# xr_vco_components.net
KiCad netlist of a schematic drawn in EAGLE
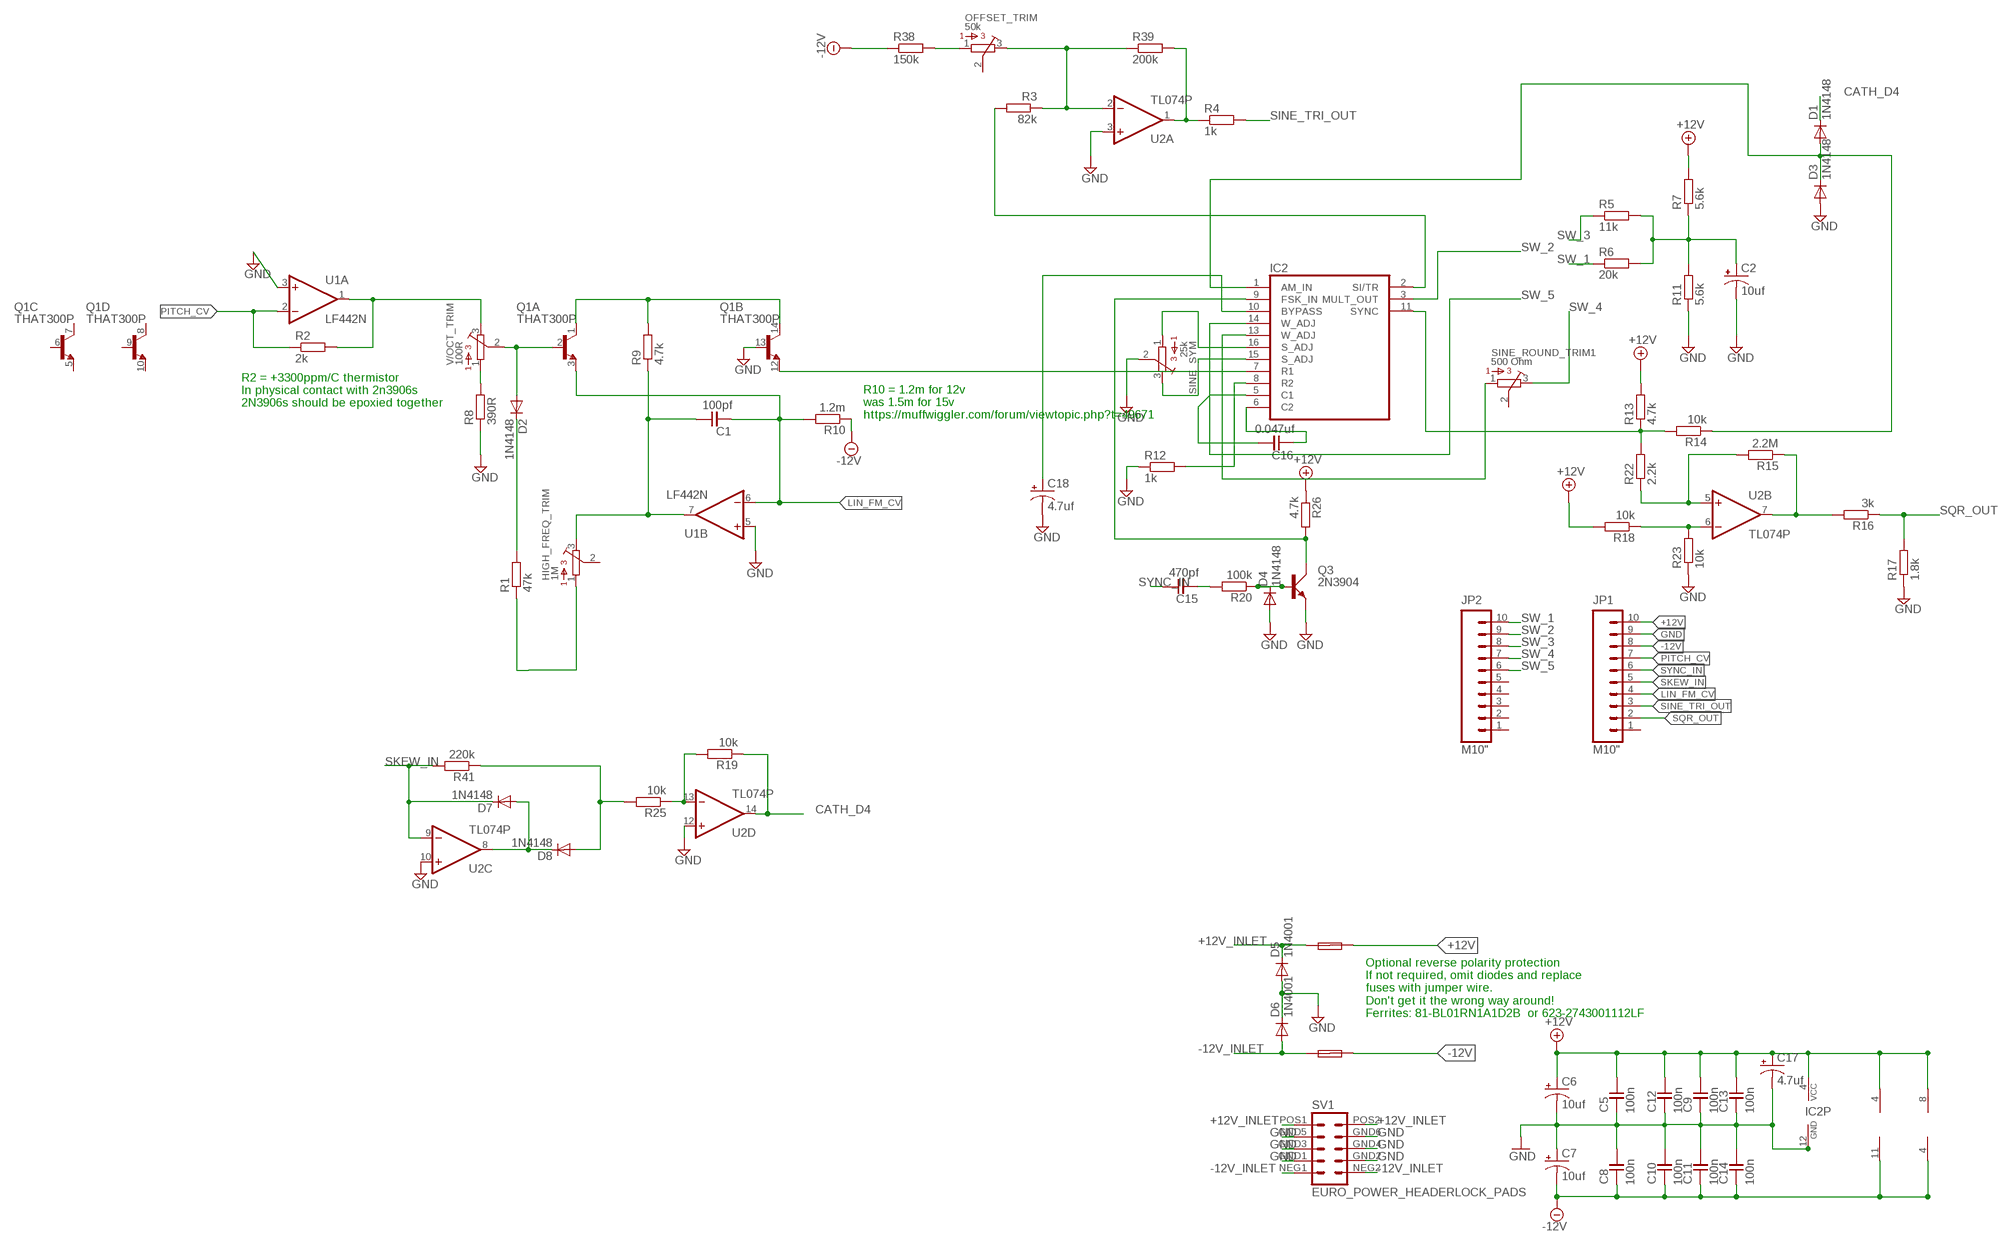
[diagram p0: schematic, sheet 1]

(export (version "E")
  (design (tool "Eeschema 10.0.6"))
  (components
    (comp (ref "C1")
      (value "100pf")
      (footprint "eagle-import:C050-024X044")
      (libsource (lib "eagle-import") (part "C-EU050-024X044"))
    )
    (comp (ref "C2")
      (value "10uf")
      (footprint "eagle-import:CPOL-RADIAL-10UF-25V")
      (libsource (lib "eagle-import") (part "CAP_POLPTH2"))
    )
    (comp (ref "C5")
      (value "100n")
      (footprint "eagle-import:C050-024X044")
      (libsource (lib "eagle-import") (part "C-EU050-024X044"))
    )
    (comp (ref "C6")
      (value "10uf")
      (footprint "eagle-import:CPOL-RADIAL-10UF-25V")
      (libsource (lib "eagle-import") (part "CAP_POLPTH2"))
    )
    (comp (ref "C7")
      (value "10uf")
      (footprint "eagle-import:CPOL-RADIAL-10UF-25V")
      (libsource (lib "eagle-import") (part "CAP_POLPTH2"))
    )
    (comp (ref "C8")
      (value "100n")
      (footprint "eagle-import:C050-024X044")
      (libsource (lib "eagle-import") (part "C-EU050-024X044"))
    )
    (comp (ref "C9")
      (value "100n")
      (footprint "eagle-import:C050-024X044")
      (libsource (lib "eagle-import") (part "C-EU050-024X044"))
    )
    (comp (ref "C10")
      (value "100n")
      (footprint "eagle-import:C050-024X044")
      (libsource (lib "eagle-import") (part "C-EU050-024X044"))
    )
    (comp (ref "C11")
      (value "100n")
      (footprint "eagle-import:C050-024X044")
      (libsource (lib "eagle-import") (part "C-EU050-024X044"))
    )
    (comp (ref "C12")
      (value "100n")
      (footprint "eagle-import:C050-024X044")
      (libsource (lib "eagle-import") (part "C-EU050-024X044"))
    )
    (comp (ref "C13")
      (value "100n")
      (footprint "eagle-import:C050-024X044")
      (libsource (lib "eagle-import") (part "C-EU050-024X044"))
    )
    (comp (ref "C14")
      (value "100n")
      (footprint "eagle-import:C050-024X044")
      (libsource (lib "eagle-import") (part "C-EU050-024X044"))
    )
    (comp (ref "C15")
      (value "470pf")
      (footprint "eagle-import:C050-024X044")
      (libsource (lib "eagle-import") (part "C-EU050-024X044"))
    )
    (comp (ref "C16")
      (value "0.047uf")
      (footprint "eagle-import:C050-024X044")
      (libsource (lib "eagle-import") (part "C-EU050-024X044"))
    )
    (comp (ref "C17")
      (value "4.7uf")
      (footprint "eagle-import:CPOL-RADIAL-10UF-25V")
      (libsource (lib "eagle-import") (part "CAP_POLPTH2"))
    )
    (comp (ref "C18")
      (value "4.7uf")
      (footprint "eagle-import:CPOL-RADIAL-10UF-25V")
      (libsource (lib "eagle-import") (part "CAP_POLPTH2"))
    )
    (comp (ref "D1")
      (value "1N4148")
      (footprint "eagle-import:DO35-7")
      (libsource (lib "eagle-import") (part "SMALL_DIODEDO35-7"))
    )
    (comp (ref "D2")
      (value "1N4148")
      (footprint "eagle-import:DO35-7")
      (libsource (lib "eagle-import") (part "SMALL_DIODEDO35-7"))
    )
    (comp (ref "D3")
      (value "1N4148")
      (footprint "eagle-import:DO35-7")
      (libsource (lib "eagle-import") (part "SMALL_DIODEDO35-7"))
    )
    (comp (ref "D4")
      (value "1N4148")
      (footprint "eagle-import:DO35-7")
      (libsource (lib "eagle-import") (part "SMALL_DIODEDO35-7"))
    )
    (comp (ref "D5")
      (value "1N4001")
      (footprint "eagle-import:DO41-10")
      (libsource (lib "eagle-import") (part "1N4004"))
    )
    (comp (ref "D6")
      (value "1N4001")
      (footprint "eagle-import:DO41-10")
      (libsource (lib "eagle-import") (part "1N4004"))
    )
    (comp (ref "D7")
      (value "1N4148")
      (footprint "eagle-import:DO35-7")
      (libsource (lib "eagle-import") (part "SMALL_DIODEDO35-7"))
    )
    (comp (ref "D8")
      (value "1N4148")
      (footprint "eagle-import:DO35-7")
      (libsource (lib "eagle-import") (part "SMALL_DIODEDO35-7"))
    )
    (comp (ref "F1")
      (value "FUSE")
      (footprint "eagle-import:C050H075X075")
      (libsource (lib "eagle-import") (part "PTC_FUSEPOLY_FUSE"))
    )
    (comp (ref "F2")
      (value "FUSE")
      (footprint "eagle-import:C050H075X075")
      (libsource (lib "eagle-import") (part "PTC_FUSEPOLY_FUSE"))
    )
    (comp (ref "HIGH_FREQ_TRIM")
      (value "1M")
      (footprint "eagle-import:BOURNS_3362P_TRIMMER")
      (libsource (lib "eagle-import") (part "BOURNS_3362P_TRIMMERP"))
    )
    (comp (ref "IC2")
      (value "XR-2206")
      (footprint "eagle-import:DIL16")
      (libsource (lib "eagle-import") (part "XR-2206"))
    )
    (comp (ref "JP1")
      (value "M10\"")
      (footprint "eagle-import:1X10")
      (libsource (lib "eagle-import") (part "M10{dblquote}"))
    )
    (comp (ref "JP2")
      (value "M10\"")
      (footprint "eagle-import:1X10")
      (libsource (lib "eagle-import") (part "M10{dblquote}"))
    )
    (comp (ref "OFFSET_TRIM")
      (value "50k")
      (footprint "eagle-import:BOURNS_3362P_TRIMMER")
      (libsource (lib "eagle-import") (part "BOURNS_3362P_TRIMMERP"))
    )
    (comp (ref "Q1")
      (value "THAT300P")
      (footprint "eagle-import:DIL14")
      (libsource (lib "eagle-import") (part "THAT300P"))
    )
    (comp (ref "Q3")
      (value "2N3904")
      (footprint "eagle-import:TO92D")
      (libsource (lib "eagle-import") (part "2N3904"))
    )
    (comp (ref "R1")
      (value "47k")
      (footprint "eagle-import:7MM_RESISTOR")
      (libsource (lib "eagle-import") (part "RESISTOR7MM"))
    )
    (comp (ref "R2")
      (value "2k")
      (footprint "eagle-import:7MM_RESISTOR")
      (libsource (lib "eagle-import") (part "RESISTOR7MM"))
    )
    (comp (ref "R3")
      (value "82k")
      (footprint "eagle-import:7MM_RESISTOR")
      (libsource (lib "eagle-import") (part "RESISTOR7MM"))
    )
    (comp (ref "R4")
      (value "1k")
      (footprint "eagle-import:7MM_RESISTOR")
      (libsource (lib "eagle-import") (part "RESISTOR7MM"))
    )
    (comp (ref "R5")
      (value "11k")
      (footprint "eagle-import:7MM_RESISTOR")
      (libsource (lib "eagle-import") (part "RESISTOR7MM"))
    )
    (comp (ref "R6")
      (value "20k")
      (footprint "eagle-import:7MM_RESISTOR")
      (libsource (lib "eagle-import") (part "RESISTOR7MM"))
    )
    (comp (ref "R7")
      (value "5.6k")
      (footprint "eagle-import:7MM_RESISTOR")
      (libsource (lib "eagle-import") (part "RESISTOR7MM"))
    )
    (comp (ref "R8")
      (value "390R")
      (footprint "eagle-import:7MM_RESISTOR")
      (libsource (lib "eagle-import") (part "RESISTOR7MM"))
    )
    (comp (ref "R9")
      (value "4.7k")
      (footprint "eagle-import:7MM_RESISTOR")
      (libsource (lib "eagle-import") (part "RESISTOR7MM"))
    )
    (comp (ref "R10")
      (value "1.2m")
      (footprint "eagle-import:7MM_RESISTOR")
      (libsource (lib "eagle-import") (part "RESISTOR7MM"))
    )
    (comp (ref "R11")
      (value "5.6k")
      (footprint "eagle-import:7MM_RESISTOR")
      (libsource (lib "eagle-import") (part "RESISTOR7MM"))
    )
    (comp (ref "R12")
      (value "1k")
      (footprint "eagle-import:7MM_RESISTOR")
      (libsource (lib "eagle-import") (part "RESISTOR7MM"))
    )
    (comp (ref "R13")
      (value "4.7k")
      (footprint "eagle-import:7MM_RESISTOR")
      (libsource (lib "eagle-import") (part "RESISTOR7MM"))
    )
    (comp (ref "R14")
      (value "10k")
      (footprint "eagle-import:7MM_RESISTOR")
      (libsource (lib "eagle-import") (part "RESISTOR7MM"))
    )
    (comp (ref "R15")
      (value "2.2M")
      (footprint "eagle-import:7MM_RESISTOR")
      (libsource (lib "eagle-import") (part "RESISTOR7MM"))
    )
    (comp (ref "R16")
      (value "3k")
      (footprint "eagle-import:7MM_RESISTOR")
      (libsource (lib "eagle-import") (part "RESISTOR7MM"))
    )
    (comp (ref "R17")
      (value "1.8k")
      (footprint "eagle-import:7MM_RESISTOR")
      (libsource (lib "eagle-import") (part "RESISTOR7MM"))
    )
    (comp (ref "R18")
      (value "10k")
      (footprint "eagle-import:7MM_RESISTOR")
      (libsource (lib "eagle-import") (part "RESISTOR7MM"))
    )
    (comp (ref "R19")
      (value "10k")
      (footprint "eagle-import:7MM_RESISTOR")
      (libsource (lib "eagle-import") (part "RESISTOR7MM"))
    )
    (comp (ref "R20")
      (value "100k")
      (footprint "eagle-import:7MM_RESISTOR")
      (libsource (lib "eagle-import") (part "RESISTOR7MM"))
    )
    (comp (ref "R22")
      (value "2.2k")
      (footprint "eagle-import:7MM_RESISTOR")
      (libsource (lib "eagle-import") (part "RESISTOR7MM"))
    )
    (comp (ref "R23")
      (value "10k")
      (footprint "eagle-import:7MM_RESISTOR")
      (libsource (lib "eagle-import") (part "RESISTOR7MM"))
    )
    (comp (ref "R25")
      (value "10k")
      (footprint "eagle-import:7MM_RESISTOR")
      (libsource (lib "eagle-import") (part "RESISTOR7MM"))
    )
    (comp (ref "R26")
      (value "4.7k")
      (footprint "eagle-import:7MM_RESISTOR")
      (libsource (lib "eagle-import") (part "RESISTOR7MM"))
    )
    (comp (ref "R38")
      (value "150k")
      (footprint "eagle-import:7MM_RESISTOR")
      (libsource (lib "eagle-import") (part "RESISTOR7MM"))
    )
    (comp (ref "R39")
      (value "200k")
      (footprint "eagle-import:7MM_RESISTOR")
      (libsource (lib "eagle-import") (part "RESISTOR7MM"))
    )
    (comp (ref "R41")
      (value "220k")
      (footprint "eagle-import:7MM_RESISTOR")
      (libsource (lib "eagle-import") (part "RESISTOR7MM"))
    )
    (comp (ref "SINE_ROUND_TRIM1")
      (value "500 Ohm")
      (footprint "eagle-import:BOURNS_3362P_TRIMMER")
      (libsource (lib "eagle-import") (part "BOURNS_3362P_TRIMMERP"))
    )
    (comp (ref "SINE_SYM")
      (value "25k")
      (footprint "eagle-import:BOURNS_3362P_TRIMMER")
      (libsource (lib "eagle-import") (part "BOURNS_3362P_TRIMMERP"))
    )
    (comp (ref "SV1")
      (value "EURO_POWER_HEADERLOCK_PADS")
      (footprint "eagle-import:EURO_PWR_HEADER_LOCK")
      (libsource (lib "eagle-import") (part "EURO_POWER_HEADERLOCK_PADS"))
    )
    (comp (ref "U1")
      (value "LF442N")
      (footprint "eagle-import:DIL08")
      (libsource (lib "eagle-import") (part "LF442N"))
    )
    (comp (ref "U2")
      (value "TL074P")
      (footprint "eagle-import:DIL14")
      (libsource (lib "eagle-import") (part "TL074P"))
    )
    (comp (ref "V/OCT_TRIM")
      (value "100R")
      (footprint "eagle-import:BOURNS_3362P_TRIMMER")
      (libsource (lib "eagle-import") (part "BOURNS_3362P_TRIMMERP"))
    )
  )
  (nets
    (net (code "1") (name "+12V") (class "Default")
      (node (ref "C12") (pin "1") (pinfunction "1_1") (pintype "passive"))
      (node (ref "C13") (pin "1") (pinfunction "1_1") (pintype "passive"))
      (node (ref "C17") (pin "1") (pinfunction "+_1") (pintype "passive"))
      (node (ref "C5") (pin "1") (pinfunction "1_1") (pintype "passive"))
      (node (ref "C6") (pin "1") (pinfunction "+_1") (pintype "passive"))
      (node (ref "C9") (pin "1") (pinfunction "1_1") (pintype "passive"))
      (node (ref "F1") (pin "2") (pinfunction "P$2_2") (pintype "bidirectional"))
      (node (ref "IC2") (pin "4") (pinfunction "VCC_4") (pintype "power_in"))
      (node (ref "JP1") (pin "10") (pinfunction "10_10") (pintype "passive"))
      (node (ref "R13") (pin "2") (pinfunction "2_2") (pintype "passive"))
      (node (ref "R18") (pin "2") (pinfunction "2_2") (pintype "passive"))
      (node (ref "R26") (pin "1") (pinfunction "1_1") (pintype "passive"))
      (node (ref "R7") (pin "2") (pinfunction "2_2") (pintype "passive"))
      (node (ref "U1") (pin "8") (pinfunction "V+_8") (pintype "power_in"))
      (node (ref "U2") (pin "4") (pinfunction "V+_4") (pintype "power_in"))
    )
    (net (code "2") (name "-12V") (class "Default")
      (node (ref "C10") (pin "2") (pinfunction "2_2") (pintype "passive"))
      (node (ref "C11") (pin "2") (pinfunction "2_2") (pintype "passive"))
      (node (ref "C14") (pin "2") (pinfunction "2_2") (pintype "passive"))
      (node (ref "C7") (pin "2") (pinfunction "-_2") (pintype "passive"))
      (node (ref "C8") (pin "2") (pinfunction "2_2") (pintype "passive"))
      (node (ref "F2") (pin "2") (pinfunction "P$2_2") (pintype "bidirectional"))
      (node (ref "JP1") (pin "8") (pinfunction "8_8") (pintype "passive"))
      (node (ref "R10") (pin "1") (pinfunction "1_1") (pintype "passive"))
      (node (ref "R38") (pin "1") (pinfunction "1_1") (pintype "passive"))
      (node (ref "U1") (pin "4") (pinfunction "V-_4") (pintype "power_in"))
      (node (ref "U2") (pin "11") (pinfunction "V-_11") (pintype "power_in"))
    )
    (net (code "3") (name "/+12V_INLET") (class "Default")
      (node (ref "D5") (pin "C") (pinfunction "C_C") (pintype "passive"))
      (node (ref "F1") (pin "1") (pinfunction "P$1_1") (pintype "bidirectional"))
      (node (ref "SV1") (pin "POS1") (pinfunction "10_POS1") (pintype "passive"))
      (node (ref "SV1") (pin "POS2") (pinfunction "9_POS2") (pintype "passive"))
    )
    (net (code "4") (name "/-12V_INLET") (class "Default")
      (node (ref "D6") (pin "A") (pinfunction "A_A") (pintype "passive"))
      (node (ref "F2") (pin "1") (pinfunction "P$1_1") (pintype "bidirectional"))
      (node (ref "SV1") (pin "NEG1") (pinfunction "2_NEG1") (pintype "passive"))
      (node (ref "SV1") (pin "NEG2") (pinfunction "1_NEG2") (pintype "passive"))
    )
    (net (code "5") (name "/CATH_D4") (class "Default")
      (node (ref "D1") (pin "C") (pinfunction "C_C") (pintype "passive"))
      (node (ref "R19") (pin "1") (pinfunction "1_1") (pintype "passive"))
      (node (ref "U2") (pin "14") (pinfunction "OUT_14") (pintype "output"))
    )
    (net (code "6") (name "/SW_1") (class "Default")
      (node (ref "JP2") (pin "10") (pinfunction "10_10") (pintype "passive"))
      (node (ref "R6") (pin "1") (pinfunction "1_1") (pintype "passive"))
    )
    (net (code "7") (name "/SW_2") (class "Default")
      (node (ref "IC2") (pin "3") (pinfunction "MULT_OUT_3") (pintype "output"))
      (node (ref "JP2") (pin "9") (pinfunction "9_9") (pintype "passive"))
    )
    (net (code "8") (name "/SW_3") (class "Default")
      (node (ref "JP2") (pin "8") (pinfunction "8_8") (pintype "passive"))
      (node (ref "R5") (pin "1") (pinfunction "1_1") (pintype "passive"))
    )
    (net (code "9") (name "/SW_4") (class "Default")
      (node (ref "JP2") (pin "7") (pinfunction "7_7") (pintype "passive"))
      (node (ref "SINE_ROUND_TRIM1") (pin "3") (pinfunction "3_3") (pintype "passive"))
    )
    (net (code "10") (name "/SW_5") (class "Default")
      (node (ref "IC2") (pin "14") (pinfunction "W_ADJ_14") (pintype "input"))
      (node (ref "JP2") (pin "6") (pinfunction "6_6") (pintype "passive"))
    )
    (net (code "11") (name "GND") (class "Default")
      (node (ref "C10") (pin "1") (pinfunction "1_1") (pintype "passive"))
      (node (ref "C11") (pin "1") (pinfunction "1_1") (pintype "passive"))
      (node (ref "C12") (pin "2") (pinfunction "2_2") (pintype "passive"))
      (node (ref "C13") (pin "2") (pinfunction "2_2") (pintype "passive"))
      (node (ref "C14") (pin "1") (pinfunction "1_1") (pintype "passive"))
      (node (ref "C17") (pin "2") (pinfunction "-_2") (pintype "passive"))
      (node (ref "C18") (pin "2") (pinfunction "-_2") (pintype "passive"))
      (node (ref "C2") (pin "2") (pinfunction "-_2") (pintype "passive"))
      (node (ref "C5") (pin "2") (pinfunction "2_2") (pintype "passive"))
      (node (ref "C6") (pin "2") (pinfunction "-_2") (pintype "passive"))
      (node (ref "C7") (pin "1") (pinfunction "+_1") (pintype "passive"))
      (node (ref "C8") (pin "1") (pinfunction "1_1") (pintype "passive"))
      (node (ref "C9") (pin "2") (pinfunction "2_2") (pintype "passive"))
      (node (ref "D3") (pin "A") (pinfunction "A_A") (pintype "passive"))
      (node (ref "D4") (pin "A") (pinfunction "A_A") (pintype "passive"))
      (node (ref "D5") (pin "A") (pinfunction "A_A") (pintype "passive"))
      (node (ref "D6") (pin "C") (pinfunction "C_C") (pintype "passive"))
      (node (ref "IC2") (pin "12") (pinfunction "GND_12") (pintype "power_in"))
      (node (ref "JP1") (pin "9") (pinfunction "9_9") (pintype "passive"))
      (node (ref "Q1") (pin "13") (pinfunction "B_13") (pintype "passive"))
      (node (ref "Q3") (pin "E") (pinfunction "E_E") (pintype "passive"))
      (node (ref "R11") (pin "1") (pinfunction "1_1") (pintype "passive"))
      (node (ref "R12") (pin "1") (pinfunction "1_1") (pintype "passive"))
      (node (ref "R17") (pin "1") (pinfunction "1_1") (pintype "passive"))
      (node (ref "R23") (pin "1") (pinfunction "1_1") (pintype "passive"))
      (node (ref "R8") (pin "1") (pinfunction "1_1") (pintype "passive"))
      (node (ref "SINE_SYM") (pin "2") (pinfunction "2_2") (pintype "passive"))
      (node (ref "SV1") (pin "GND1") (pinfunction "4_GND1") (pintype "passive"))
      (node (ref "SV1") (pin "GND2") (pinfunction "3_GND2") (pintype "passive"))
      (node (ref "SV1") (pin "GND3") (pinfunction "6_GND3") (pintype "passive"))
      (node (ref "SV1") (pin "GND4") (pinfunction "5_GND4") (pintype "passive"))
      (node (ref "SV1") (pin "GND5") (pinfunction "8_GND5") (pintype "passive"))
      (node (ref "SV1") (pin "GND6") (pinfunction "7_GND6") (pintype "passive"))
      (node (ref "U1") (pin "3") (pinfunction "+IN_3") (pintype "input"))
      (node (ref "U1") (pin "5") (pinfunction "+IN_5") (pintype "input"))
      (node (ref "U2") (pin "10") (pinfunction "+IN_10") (pintype "input"))
      (node (ref "U2") (pin "12") (pinfunction "+IN_12") (pintype "input"))
      (node (ref "U2") (pin "3") (pinfunction "+IN_3") (pintype "input"))
    )
    (net (code "12") (name "LIN_FM_CV") (class "Default")
      (node (ref "C1") (pin "2") (pinfunction "2_2") (pintype "passive"))
      (node (ref "JP1") (pin "4") (pinfunction "4_4") (pintype "passive"))
      (node (ref "Q1") (pin "3") (pinfunction "E_3") (pintype "passive"))
      (node (ref "R10") (pin "2") (pinfunction "2_2") (pintype "passive"))
      (node (ref "U1") (pin "6") (pinfunction "-IN_6") (pintype "input"))
    )
    (net (code "13") (name "Net-(C2-+)") (class "Default")
      (node (ref "C2") (pin "1") (pinfunction "+_1") (pintype "passive"))
      (node (ref "R11") (pin "2") (pinfunction "2_2") (pintype "passive"))
      (node (ref "R5") (pin "2") (pinfunction "2_2") (pintype "passive"))
      (node (ref "R6") (pin "2") (pinfunction "2_2") (pintype "passive"))
      (node (ref "R7") (pin "1") (pinfunction "1_1") (pintype "passive"))
    )
    (net (code "14") (name "Net-(C15-Pad2)") (class "Default")
      (node (ref "C15") (pin "2") (pinfunction "2_2") (pintype "passive"))
      (node (ref "R20") (pin "2") (pinfunction "2_2") (pintype "passive"))
    )
    (net (code "15") (name "Net-(C18-+)") (class "Default")
      (node (ref "C18") (pin "1") (pinfunction "+_1") (pintype "passive"))
      (node (ref "IC2") (pin "10") (pinfunction "BYPASS_10") (pintype "input"))
    )
    (net (code "16") (name "Net-(D2-PadC)") (class "Default")
      (node (ref "D2") (pin "C") (pinfunction "C_C") (pintype "passive"))
      (node (ref "R1") (pin "2") (pinfunction "2_2") (pintype "passive"))
    )
    (net (code "17") (name "Net-(D4-PadC)") (class "Default")
      (node (ref "D4") (pin "C") (pinfunction "C_C") (pintype "passive"))
      (node (ref "Q3") (pin "B") (pinfunction "B_B") (pintype "passive"))
      (node (ref "R20") (pin "1") (pinfunction "1_1") (pintype "passive"))
    )
    (net (code "18") (name "Net-(D8-PadA)") (class "Default")
      (node (ref "D8") (pin "A") (pinfunction "A_A") (pintype "passive"))
      (node (ref "R25") (pin "2") (pinfunction "2_2") (pintype "passive"))
      (node (ref "R41") (pin "1") (pinfunction "1_1") (pintype "passive"))
    )
    (net (code "19") (name "Net-(HIGH_FREQ_TRIM-Pad1)") (class "Default")
      (node (ref "HIGH_FREQ_TRIM") (pin "1") (pinfunction "1_1") (pintype "passive"))
      (node (ref "R1") (pin "1") (pinfunction "1_1") (pintype "passive"))
    )
    (net (code "20") (name "Net-(IC2A-AM_IN)") (class "Default")
      (node (ref "D1") (pin "A") (pinfunction "A_A") (pintype "passive"))
      (node (ref "D3") (pin "C") (pinfunction "C_C") (pintype "passive"))
      (node (ref "IC2") (pin "1") (pinfunction "AM_IN_1") (pintype "input"))
      (node (ref "R14") (pin "1") (pinfunction "1_1") (pintype "passive"))
    )
    (net (code "21") (name "Net-(IC2A-C1)") (class "Default")
      (node (ref "C16") (pin "1") (pinfunction "1_1") (pintype "passive"))
      (node (ref "IC2") (pin "5") (pinfunction "C1_5") (pintype "input"))
    )
    (net (code "22") (name "Net-(IC2A-C2)") (class "Default")
      (node (ref "C16") (pin "2") (pinfunction "2_2") (pintype "passive"))
      (node (ref "IC2") (pin "6") (pinfunction "C2_6") (pintype "input"))
    )
    (net (code "23") (name "Net-(IC2A-FSK_IN)") (class "Default")
      (node (ref "IC2") (pin "9") (pinfunction "FSK_IN_9") (pintype "input"))
      (node (ref "Q3") (pin "C") (pinfunction "C_C") (pintype "passive"))
      (node (ref "R26") (pin "2") (pinfunction "2_2") (pintype "passive"))
    )
    (net (code "24") (name "Net-(IC2A-R1)") (class "Default")
      (node (ref "IC2") (pin "7") (pinfunction "R1_7") (pintype "input"))
      (node (ref "Q1") (pin "12") (pinfunction "E_12") (pintype "passive"))
    )
    (net (code "25") (name "Net-(IC2A-R2)") (class "Default")
      (node (ref "IC2") (pin "8") (pinfunction "R2_8") (pintype "input"))
      (node (ref "R12") (pin "2") (pinfunction "2_2") (pintype "passive"))
    )
    (net (code "26") (name "Net-(IC2A-SI{slash}TR)") (class "Default")
      (node (ref "IC2") (pin "2") (pinfunction "SI/TR_2") (pintype "output"))
      (node (ref "R3") (pin "2") (pinfunction "2_2") (pintype "passive"))
    )
    (net (code "27") (name "Net-(IC2A-SYNC)") (class "Default")
      (node (ref "IC2") (pin "11") (pinfunction "SYNC_11") (pintype "output"))
      (node (ref "R13") (pin "1") (pinfunction "1_1") (pintype "passive"))
      (node (ref "R14") (pin "2") (pinfunction "2_2") (pintype "passive"))
      (node (ref "R22") (pin "2") (pinfunction "2_2") (pintype "passive"))
    )
    (net (code "28") (name "Net-(IC2A-S_ADJ-Pad15)") (class "Default")
      (node (ref "IC2") (pin "15") (pinfunction "S_ADJ_15") (pintype "input"))
      (node (ref "SINE_SYM") (pin "3") (pinfunction "3_3") (pintype "passive"))
    )
    (net (code "29") (name "Net-(IC2A-S_ADJ-Pad16)") (class "Default")
      (node (ref "IC2") (pin "16") (pinfunction "S_ADJ_16") (pintype "input"))
      (node (ref "SINE_SYM") (pin "1") (pinfunction "1_1") (pintype "passive"))
    )
    (net (code "30") (name "Net-(IC2A-W_ADJ-Pad13)") (class "Default")
      (node (ref "IC2") (pin "13") (pinfunction "W_ADJ_13") (pintype "input"))
      (node (ref "SINE_ROUND_TRIM1") (pin "1") (pinfunction "1_1") (pintype "passive"))
    )
    (net (code "31") (name "Net-(OFFSET_TRIM-Pad1)") (class "Default")
      (node (ref "OFFSET_TRIM") (pin "1") (pinfunction "1_1") (pintype "passive"))
      (node (ref "R38") (pin "2") (pinfunction "2_2") (pintype "passive"))
    )
    (net (code "32") (name "Net-(Q1A-B)") (class "Default")
      (node (ref "D2") (pin "A") (pinfunction "A_A") (pintype "passive"))
      (node (ref "Q1") (pin "2") (pinfunction "B_2") (pintype "passive"))
      (node (ref "V/OCT_TRIM") (pin "2") (pinfunction "2_2") (pintype "passive"))
    )
    (net (code "33") (name "Net-(Q1A-C)") (class "Default")
      (node (ref "Q1") (pin "1") (pinfunction "C_1") (pintype "passive"))
      (node (ref "Q1") (pin "14") (pinfunction "C_14") (pintype "passive"))
      (node (ref "R9") (pin "2") (pinfunction "2_2") (pintype "passive"))
    )
    (net (code "34") (name "Net-(R8-Pad2)") (class "Default")
      (node (ref "R8") (pin "2") (pinfunction "2_2") (pintype "passive"))
      (node (ref "V/OCT_TRIM") (pin "1") (pinfunction "1_1") (pintype "passive"))
    )
    (net (code "35") (name "Net-(U1A-OUT)") (class "Default")
      (node (ref "R2") (pin "2") (pinfunction "2_2") (pintype "passive"))
      (node (ref "U1") (pin "1") (pinfunction "OUT_1") (pintype "output"))
      (node (ref "V/OCT_TRIM") (pin "3") (pinfunction "3_3") (pintype "passive"))
    )
    (net (code "36") (name "Net-(U1B-OUT)") (class "Default")
      (node (ref "C1") (pin "1") (pinfunction "1_1") (pintype "passive"))
      (node (ref "HIGH_FREQ_TRIM") (pin "3") (pinfunction "3_3") (pintype "passive"))
      (node (ref "R9") (pin "1") (pinfunction "1_1") (pintype "passive"))
      (node (ref "U1") (pin "7") (pinfunction "OUT_7") (pintype "output"))
    )
    (net (code "37") (name "Net-(U2A--IN)") (class "Default")
      (node (ref "OFFSET_TRIM") (pin "3") (pinfunction "3_3") (pintype "passive"))
      (node (ref "R3") (pin "1") (pinfunction "1_1") (pintype "passive"))
      (node (ref "R39") (pin "1") (pinfunction "1_1") (pintype "passive"))
      (node (ref "U2") (pin "2") (pinfunction "-IN_2") (pintype "input"))
    )
    (net (code "38") (name "Net-(U2A-OUT)") (class "Default")
      (node (ref "R39") (pin "2") (pinfunction "2_2") (pintype "passive"))
      (node (ref "R4") (pin "1") (pinfunction "1_1") (pintype "passive"))
      (node (ref "U2") (pin "1") (pinfunction "OUT_1") (pintype "output"))
    )
    (net (code "39") (name "Net-(U2B-+IN)") (class "Default")
      (node (ref "R15") (pin "2") (pinfunction "2_2") (pintype "passive"))
      (node (ref "R22") (pin "1") (pinfunction "1_1") (pintype "passive"))
      (node (ref "U2") (pin "5") (pinfunction "+IN_5") (pintype "input"))
    )
    (net (code "40") (name "Net-(U2B--IN)") (class "Default")
      (node (ref "R18") (pin "1") (pinfunction "1_1") (pintype "passive"))
      (node (ref "R23") (pin "2") (pinfunction "2_2") (pintype "passive"))
      (node (ref "U2") (pin "6") (pinfunction "-IN_6") (pintype "input"))
    )
    (net (code "41") (name "Net-(U2B-OUT)") (class "Default")
      (node (ref "R15") (pin "1") (pinfunction "1_1") (pintype "passive"))
      (node (ref "R16") (pin "2") (pinfunction "2_2") (pintype "passive"))
      (node (ref "U2") (pin "7") (pinfunction "OUT_7") (pintype "output"))
    )
    (net (code "42") (name "Net-(U2C-OUT)") (class "Default")
      (node (ref "D7") (pin "A") (pinfunction "A_A") (pintype "passive"))
      (node (ref "D8") (pin "C") (pinfunction "C_C") (pintype "passive"))
      (node (ref "U2") (pin "8") (pinfunction "OUT_8") (pintype "output"))
    )
    (net (code "43") (name "Net-(U2D--IN)") (class "Default")
      (node (ref "R19") (pin "2") (pinfunction "2_2") (pintype "passive"))
      (node (ref "R25") (pin "1") (pinfunction "1_1") (pintype "passive"))
      (node (ref "U2") (pin "13") (pinfunction "-IN_13") (pintype "input"))
    )
    (net (code "44") (name "PITCH_CV") (class "Default")
      (node (ref "JP1") (pin "7") (pinfunction "7_7") (pintype "passive"))
      (node (ref "R2") (pin "1") (pinfunction "1_1") (pintype "passive"))
      (node (ref "U1") (pin "2") (pinfunction "-IN_2") (pintype "input"))
    )
    (net (code "45") (name "SINE_TRI_OUT") (class "Default")
      (node (ref "JP1") (pin "3") (pinfunction "3_3") (pintype "passive"))
      (node (ref "R4") (pin "2") (pinfunction "2_2") (pintype "passive"))
    )
    (net (code "46") (name "SKEW_IN") (class "Default")
      (node (ref "D7") (pin "C") (pinfunction "C_C") (pintype "passive"))
      (node (ref "JP1") (pin "5") (pinfunction "5_5") (pintype "passive"))
      (node (ref "R41") (pin "2") (pinfunction "2_2") (pintype "passive"))
      (node (ref "U2") (pin "9") (pinfunction "-IN_9") (pintype "input"))
    )
    (net (code "47") (name "SQR_OUT") (class "Default")
      (node (ref "JP1") (pin "2") (pinfunction "2_2") (pintype "passive"))
      (node (ref "R16") (pin "1") (pinfunction "1_1") (pintype "passive"))
      (node (ref "R17") (pin "2") (pinfunction "2_2") (pintype "passive"))
    )
    (net (code "48") (name "SYNC_IN") (class "Default")
      (node (ref "C15") (pin "1") (pinfunction "1_1") (pintype "passive"))
      (node (ref "JP1") (pin "6") (pinfunction "6_6") (pintype "passive"))
    )
    (net (code "49") (name "unconnected-(HIGH_FREQ_TRIM-Pad2)") (class "Default")
      (node (ref "HIGH_FREQ_TRIM") (pin "2") (pinfunction "2_2") (pintype "passive"))
    )
    (net (code "50") (name "unconnected-(JP1-Pad1)") (class "Default")
      (node (ref "JP1") (pin "1") (pinfunction "1_1") (pintype "passive"))
    )
    (net (code "51") (name "unconnected-(JP2-Pad1)") (class "Default")
      (node (ref "JP2") (pin "1") (pinfunction "1_1") (pintype "passive"))
    )
    (net (code "52") (name "unconnected-(JP2-Pad2)") (class "Default")
      (node (ref "JP2") (pin "2") (pinfunction "2_2") (pintype "passive"))
    )
    (net (code "53") (name "unconnected-(JP2-Pad3)") (class "Default")
      (node (ref "JP2") (pin "3") (pinfunction "3_3") (pintype "passive"))
    )
    (net (code "54") (name "unconnected-(JP2-Pad4)") (class "Default")
      (node (ref "JP2") (pin "4") (pinfunction "4_4") (pintype "passive"))
    )
    (net (code "55") (name "unconnected-(JP2-Pad5)") (class "Default")
      (node (ref "JP2") (pin "5") (pinfunction "5_5") (pintype "passive"))
    )
    (net (code "56") (name "unconnected-(OFFSET_TRIM-Pad2)") (class "Default")
      (node (ref "OFFSET_TRIM") (pin "2") (pinfunction "2_2") (pintype "passive"))
    )
    (net (code "57") (name "unconnected-(Q1C-B-Pad6)") (class "Default")
      (node (ref "Q1") (pin "6") (pinfunction "B_6") (pintype "passive"))
    )
    (net (code "58") (name "unconnected-(Q1C-C-Pad7)") (class "Default")
      (node (ref "Q1") (pin "7") (pinfunction "C_7") (pintype "passive"))
    )
    (net (code "59") (name "unconnected-(Q1C-E-Pad5)") (class "Default")
      (node (ref "Q1") (pin "5") (pinfunction "E_5") (pintype "passive"))
    )
    (net (code "60") (name "unconnected-(Q1D-B-Pad9)") (class "Default")
      (node (ref "Q1") (pin "9") (pinfunction "B_9") (pintype "passive"))
    )
    (net (code "61") (name "unconnected-(Q1D-C-Pad8)") (class "Default")
      (node (ref "Q1") (pin "8") (pinfunction "C_8") (pintype "passive"))
    )
    (net (code "62") (name "unconnected-(Q1D-E-Pad10)") (class "Default")
      (node (ref "Q1") (pin "10") (pinfunction "E_10") (pintype "passive"))
    )
    (net (code "63") (name "unconnected-(SINE_ROUND_TRIM1-Pad2)") (class "Default")
      (node (ref "SINE_ROUND_TRIM1") (pin "2") (pinfunction "2_2") (pintype "passive"))
    )
  )
)
